# dcdc-converter.net
KiCad netlist of a schematic drawn in Altium Designer
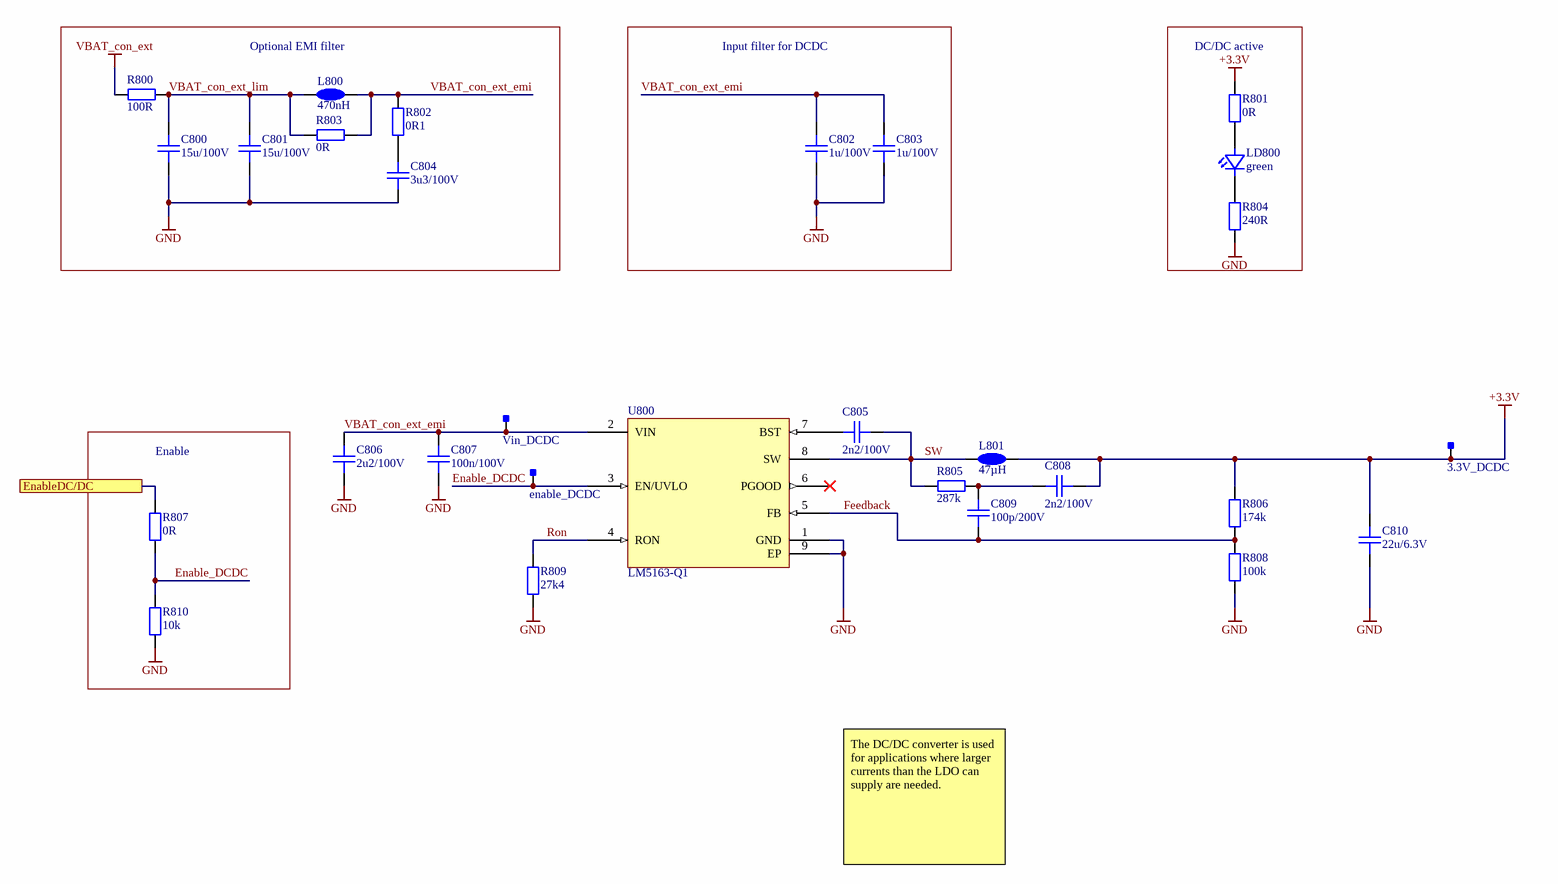
[diagram p0: dcdc-converter.SchDoc]

(export (version "E")
  (design (tool "Eeschema 10.0.6"))
  (components
    (comp (ref "3.3V_DCDC")
      (value "Testpoint_Square")
      (footprint "Testpoint_S1")
      (description "Testpoint, square")
      (libsource (lib "OE750") (part "Testpoint_Square"))
    )
    (comp (ref "C800")
      (value "15u/100V")
      (footprint "CAPC6153X67N")
      (description "Stacked MLCC")
      (fields (field (name "PART NUMBER") "gen_C_ceramic_15u_100V_X7R_2220"))
      (libsource (lib "OE750") (part "C"))
    )
    (comp (ref "C801")
      (value "15u/100V")
      (footprint "CAPC6153X67N")
      (description "Stacked MLCC")
      (fields (field (name "PART NUMBER") "gen_C_ceramic_15u_100V_X7R_2220"))
      (libsource (lib "OE750") (part "C"))
    )
    (comp (ref "C802")
      (value "1u/100V")
      (footprint "CAPC3225X25N")
      (description "MLCC")
      (fields (field (name "PART NUMBER") "gen_C_ceramic_1u_100V_X7R_1210"))
      (libsource (lib "OE750") (part "C"))
    )
    (comp (ref "C803")
      (value "1u/100V")
      (footprint "CAPC3225X25N")
      (description "MLCC")
      (fields (field (name "PART NUMBER") "gen_C_ceramic_1u_100V_X7R_1210"))
      (libsource (lib "OE750") (part "C"))
    )
    (comp (ref "C804")
      (value "3u3/100V")
      (footprint "CAPC4532X16N")
      (description "MLCC")
      (fields (field (name "PART NUMBER") "gen_C_ceramic_3u3_100V_X7R_1812"))
      (libsource (lib "OE750") (part "C"))
    )
    (comp (ref "C805")
      (value "2n2/100V")
      (footprint "CAPC1005X06N")
      (description "MLCC")
      (fields (field (name "PART NUMBER") "gen_C_ceramic_2n2_100V_X7R_0402"))
      (libsource (lib "OE750") (part "C"))
    )
    (comp (ref "C806")
      (value "2u2/100V")
      (footprint "CAPC3225X25N")
      (description "MLCC")
      (fields (field (name "PART NUMBER") "gen_C_ceramic_2u2_100V_X7R_1210"))
      (libsource (lib "OE750") (part "C"))
    )
    (comp (ref "C807")
      (value "100n/100V")
      (footprint "CAPC1608X08N")
      (description "MLCC")
      (fields (field (name "PART NUMBER") "gen_C_ceramic_100n_100V_X7R_0603"))
      (libsource (lib "OE750") (part "C"))
    )
    (comp (ref "C808")
      (value "2n2/100V")
      (footprint "CAPC1005X06N")
      (description "MLCC")
      (fields (field (name "PART NUMBER") "gen_C_ceramic_2n2_100V_X7R_0402"))
      (libsource (lib "OE750") (part "C"))
    )
    (comp (ref "C809")
      (value "100p/200V")
      (footprint "CAPC1005X06N")
      (description "MLCC")
      (fields (field (name "PART NUMBER") "gen_C_ceramic_100p_200V_C0G_0402") (field (name "TOLERANCE") "5%"))
      (libsource (lib "OE750") (part "C"))
    )
    (comp (ref "C810")
      (value "22u/6.3V")
      (footprint "CAPC3216X18N")
      (description "MLCC")
      (fields (field (name "PART NUMBER") "gen_C_ceramic_22u_6V3_X7R_1206"))
      (libsource (lib "OE750") (part "C"))
    )
    (comp (ref "enable_DCDC")
      (value "Testpoint_Square")
      (footprint "Testpoint_S1")
      (description "Testpoint, square")
      (libsource (lib "OE750") (part "Testpoint_Square"))
    )
    (comp (ref "L800")
      (value "470nH")
      (footprint "SRP7028A")
      (description "FIXED IND 470NH 17.5A 4.2 MOHM")
      (fields (field (name "PART NUMBER") "SRP7028A-R47M") (field (name "MANUFACTURER") "Bourns Inc"))
      (libsource (lib "OE750") (part "L"))
    )
    (comp (ref "L801")
      (value "47µH")
      (footprint "TYS6045470M-10")
      (description "Power Inductor")
      (fields
        (field (name "PART NUMBER") "TYS6045470M-10")
        (field (name "MANUFACTURER") "Laird-Signal Integrity Products")
      )
      (libsource (lib "OE750") (part "L"))
    )
    (comp (ref "LD800")
      (value "green")
      (footprint "LEDC1608X07N")
      (description "TLMG1100-GS08")
      (fields (field (name "PART NUMBER") "LED_0603_green_AECQ") (field (name "MANUFACTURER") "Vishay"))
      (libsource (lib "OE750") (part "D_LED"))
    )
    (comp (ref "R800")
      (value "100R")
      (footprint "RESC1608X05N")
      (description "SMD Resistor 100R 0603")
      (fields (field (name "PART NUMBER") "gen_R_100R_0603") (field (name "TOLERANCE") "1%"))
      (libsource (lib "OE750") (part "R"))
    )
    (comp (ref "R801")
      (value "0R")
      (footprint "RESC1608X05N")
      (description "SMD Resistor 0R 0603")
      (fields (field (name "PART NUMBER") "gen_R_0R_0603") (field (name "POWER") "0.1W"))
      (libsource (lib "OE750") (part "R"))
    )
    (comp (ref "R802")
      (value "0R1")
      (footprint "RESC2012X05N")
      (description "SMD Resistor 0R1 0805")
      (fields (field (name "PART NUMBER") "gen_R_0R1_0805") (field (name "POWER") "250mW"))
      (libsource (lib "OE750") (part "R"))
    )
    (comp (ref "R803")
      (value "0R")
      (footprint "RESC1608X05N")
      (description "SMD Resistor 0R 0603")
      (fields (field (name "PART NUMBER") "gen_R_0R_0603") (field (name "POWER") "0.1W"))
      (libsource (lib "OE750") (part "R"))
    )
    (comp (ref "R804")
      (value "240R")
      (footprint "RESC1608X05N")
      (description "SMD Resistor 240R 0603")
      (fields (field (name "PART NUMBER") "gen_R_240R_0603") (field (name "TOLERANCE") "1%"))
      (libsource (lib "OE750") (part "R"))
    )
    (comp (ref "R805")
      (value "287k")
      (footprint "RESC1608X05N")
      (description "SMD Resistor 287k 0603")
      (fields (field (name "PART NUMBER") "gen_R_287k_0603") (field (name "TOLERANCE") "1%"))
      (libsource (lib "OE750") (part "R"))
    )
    (comp (ref "R806")
      (value "174k")
      (footprint "RESC1608X05N")
      (description "SMD Resistor 174k 0603")
      (fields (field (name "PART NUMBER") "gen_R_174k_0603") (field (name "TOLERANCE") "1%"))
      (libsource (lib "OE750") (part "R"))
    )
    (comp (ref "R807")
      (value "0R")
      (footprint "RESC1608X05N")
      (description "SMD Resistor 0R 0603")
      (fields (field (name "PART NUMBER") "gen_R_0R_0603") (field (name "POWER") "0.1W"))
      (libsource (lib "OE750") (part "R"))
    )
    (comp (ref "R808")
      (value "100k")
      (footprint "RESC1608X05N")
      (description "SMD Resistor 100k 0603")
      (fields (field (name "PART NUMBER") "gen_R_100k_0603") (field (name "TOLERANCE") "1%"))
      (libsource (lib "OE750") (part "R"))
    )
    (comp (ref "R809")
      (value "27k4")
      (footprint "RESC1608X05N")
      (description "SMD Resistor 27k4 0603")
      (fields (field (name "PART NUMBER") "gen_R_27k4_0603") (field (name "TOLERANCE") "1%"))
      (libsource (lib "OE750") (part "R"))
    )
    (comp (ref "R810")
      (value "10k")
      (footprint "RESC1608X05N")
      (description "SMD Resistor 10k 0603")
      (fields (field (name "PART NUMBER") "gen_R_10k_0603") (field (name "TOLERANCE") "1%"))
      (libsource (lib "OE750") (part "R"))
    )
    (comp (ref "U800")
      (value "LM5163-Q1")
      (footprint "R-PDSO-G8")
      (description "100-V Input, 0.5-A SynchronousBuck DC/DCConverterwith Ultra-lowIQ")
      (fields (field (name "MANUFACTURER") "Texas Instruments"))
      (libsource (lib "OE750") (part "LM5163"))
    )
    (comp (ref "Vin_DCDC")
      (value "Testpoint_Square")
      (footprint "Testpoint_S1")
      (description "Testpoint, square")
      (libsource (lib "OE750") (part "Testpoint_Square"))
    )
  )
  (nets
    (net (code "1") (name "+3.3V") (class "Default")
      (node (ref "3.3V_DCDC") (pin "1") (pinfunction "1_1") (pintype "passive"))
      (node (ref "C808") (pin "2") (pinfunction "2_2") (pintype "passive"))
      (node (ref "C810") (pin "2") (pinfunction "2_2") (pintype "passive"))
      (node (ref "L801") (pin "2") (pinfunction "2_2") (pintype "passive"))
      (node (ref "R801") (pin "2") (pinfunction "2_2") (pintype "passive"))
      (node (ref "R806") (pin "2") (pinfunction "2_2") (pintype "passive"))
    )
    (net (code "2") (name "/EnableDC{slash}DC") (class "Default")
      (node (ref "R807") (pin "1") (pinfunction "1_1") (pintype "passive"))
    )
    (net (code "3") (name "/Enable_DCDC") (class "Default")
      (node (ref "R807") (pin "2") (pinfunction "2_2") (pintype "passive"))
      (node (ref "R810") (pin "1") (pinfunction "1_1") (pintype "passive"))
      (node (ref "U800") (pin "3") (pinfunction "EN/UVLO_3") (pintype "input"))
      (node (ref "enable_DCDC") (pin "1") (pinfunction "1_1") (pintype "passive"))
    )
    (net (code "4") (name "/Feedback") (class "Default")
      (node (ref "C809") (pin "1") (pinfunction "1_1") (pintype "passive"))
      (node (ref "R806") (pin "1") (pinfunction "1_1") (pintype "passive"))
      (node (ref "R808") (pin "2") (pinfunction "2_2") (pintype "passive"))
      (node (ref "U800") (pin "5") (pinfunction "FB_5") (pintype "input"))
    )
    (net (code "5") (name "/Ron") (class "Default")
      (node (ref "R809") (pin "2") (pinfunction "2_2") (pintype "passive"))
      (node (ref "U800") (pin "4") (pinfunction "RON_4") (pintype "input"))
    )
    (net (code "6") (name "/SW") (class "Default")
      (node (ref "C805") (pin "2") (pinfunction "2_2") (pintype "passive"))
      (node (ref "L801") (pin "1") (pinfunction "1_1") (pintype "passive"))
      (node (ref "R805") (pin "1") (pinfunction "1_1") (pintype "passive"))
      (node (ref "U800") (pin "8") (pinfunction "SW_8") (pintype "power_in"))
    )
    (net (code "7") (name "/VBAT_con_ext_emi") (class "Default")
      (node (ref "C802") (pin "2") (pinfunction "2_2") (pintype "passive"))
      (node (ref "C803") (pin "2") (pinfunction "2_2") (pintype "passive"))
      (node (ref "C806") (pin "2") (pinfunction "2_2") (pintype "passive"))
      (node (ref "C807") (pin "2") (pinfunction "2_2") (pintype "passive"))
      (node (ref "L800") (pin "2") (pinfunction "2_2") (pintype "passive"))
      (node (ref "R802") (pin "2") (pinfunction "2_2") (pintype "passive"))
      (node (ref "R803") (pin "2") (pinfunction "2_2") (pintype "passive"))
      (node (ref "U800") (pin "2") (pinfunction "VIN_2") (pintype "power_in"))
      (node (ref "Vin_DCDC") (pin "1") (pinfunction "1_1") (pintype "passive"))
    )
    (net (code "8") (name "/VBAT_con_ext_lim") (class "Default")
      (node (ref "C800") (pin "2") (pinfunction "2_2") (pintype "passive"))
      (node (ref "C801") (pin "2") (pinfunction "2_2") (pintype "passive"))
      (node (ref "L800") (pin "1") (pinfunction "1_1") (pintype "passive"))
      (node (ref "R800") (pin "2") (pinfunction "2_2") (pintype "passive"))
      (node (ref "R803") (pin "1") (pinfunction "1_1") (pintype "passive"))
    )
    (net (code "9") (name "GND") (class "Default")
      (node (ref "C800") (pin "1") (pinfunction "1_1") (pintype "passive"))
      (node (ref "C801") (pin "1") (pinfunction "1_1") (pintype "passive"))
      (node (ref "C802") (pin "1") (pinfunction "1_1") (pintype "passive"))
      (node (ref "C803") (pin "1") (pinfunction "1_1") (pintype "passive"))
      (node (ref "C804") (pin "1") (pinfunction "1_1") (pintype "passive"))
      (node (ref "C806") (pin "1") (pinfunction "1_1") (pintype "passive"))
      (node (ref "C807") (pin "1") (pinfunction "1_1") (pintype "passive"))
      (node (ref "C810") (pin "1") (pinfunction "1_1") (pintype "passive"))
      (node (ref "R804") (pin "1") (pinfunction "1_1") (pintype "passive"))
      (node (ref "R808") (pin "1") (pinfunction "1_1") (pintype "passive"))
      (node (ref "R809") (pin "1") (pinfunction "1_1") (pintype "passive"))
      (node (ref "R810") (pin "2") (pinfunction "2_2") (pintype "passive"))
      (node (ref "U800") (pin "1") (pinfunction "GND_1") (pintype "power_in"))
      (node (ref "U800") (pin "9") (pinfunction "EP_9") (pintype "power_in"))
    )
    (net (code "10") (name "Net-(C804-Pad2)") (class "Default")
      (node (ref "C804") (pin "2") (pinfunction "2_2") (pintype "passive"))
      (node (ref "R802") (pin "1") (pinfunction "1_1") (pintype "passive"))
    )
    (net (code "11") (name "Net-(C808-Pad1)") (class "Default")
      (node (ref "C808") (pin "1") (pinfunction "1_1") (pintype "passive"))
      (node (ref "C809") (pin "2") (pinfunction "2_2") (pintype "passive"))
      (node (ref "R805") (pin "2") (pinfunction "2_2") (pintype "passive"))
    )
    (net (code "12") (name "Net-(LD800-A)") (class "Default")
      (node (ref "LD800") (pin "2") (pinfunction "A_2") (pintype "passive"))
      (node (ref "R801") (pin "1") (pinfunction "1_1") (pintype "passive"))
    )
    (net (code "13") (name "Net-(LD800-C)") (class "Default")
      (node (ref "LD800") (pin "1") (pinfunction "C_1") (pintype "passive"))
      (node (ref "R804") (pin "2") (pinfunction "2_2") (pintype "passive"))
    )
    (net (code "14") (name "Net-(U800-BST)") (class "Default")
      (node (ref "C805") (pin "1") (pinfunction "1_1") (pintype "passive"))
      (node (ref "U800") (pin "7") (pinfunction "BST_7") (pintype "input"))
    )
    (net (code "15") (name "VBAT_con_ext") (class "Default")
      (node (ref "R800") (pin "1") (pinfunction "1_1") (pintype "passive"))
    )
    (net (code "16") (name "unconnected-(U800-PGOOD-Pad6)") (class "Default")
      (node (ref "U800") (pin "6") (pinfunction "PGOOD_6") (pintype "output+no_connect"))
    )
  )
)
